# RAM_GPIO.net
KiCad netlist of a schematic drawn in Altium Designer
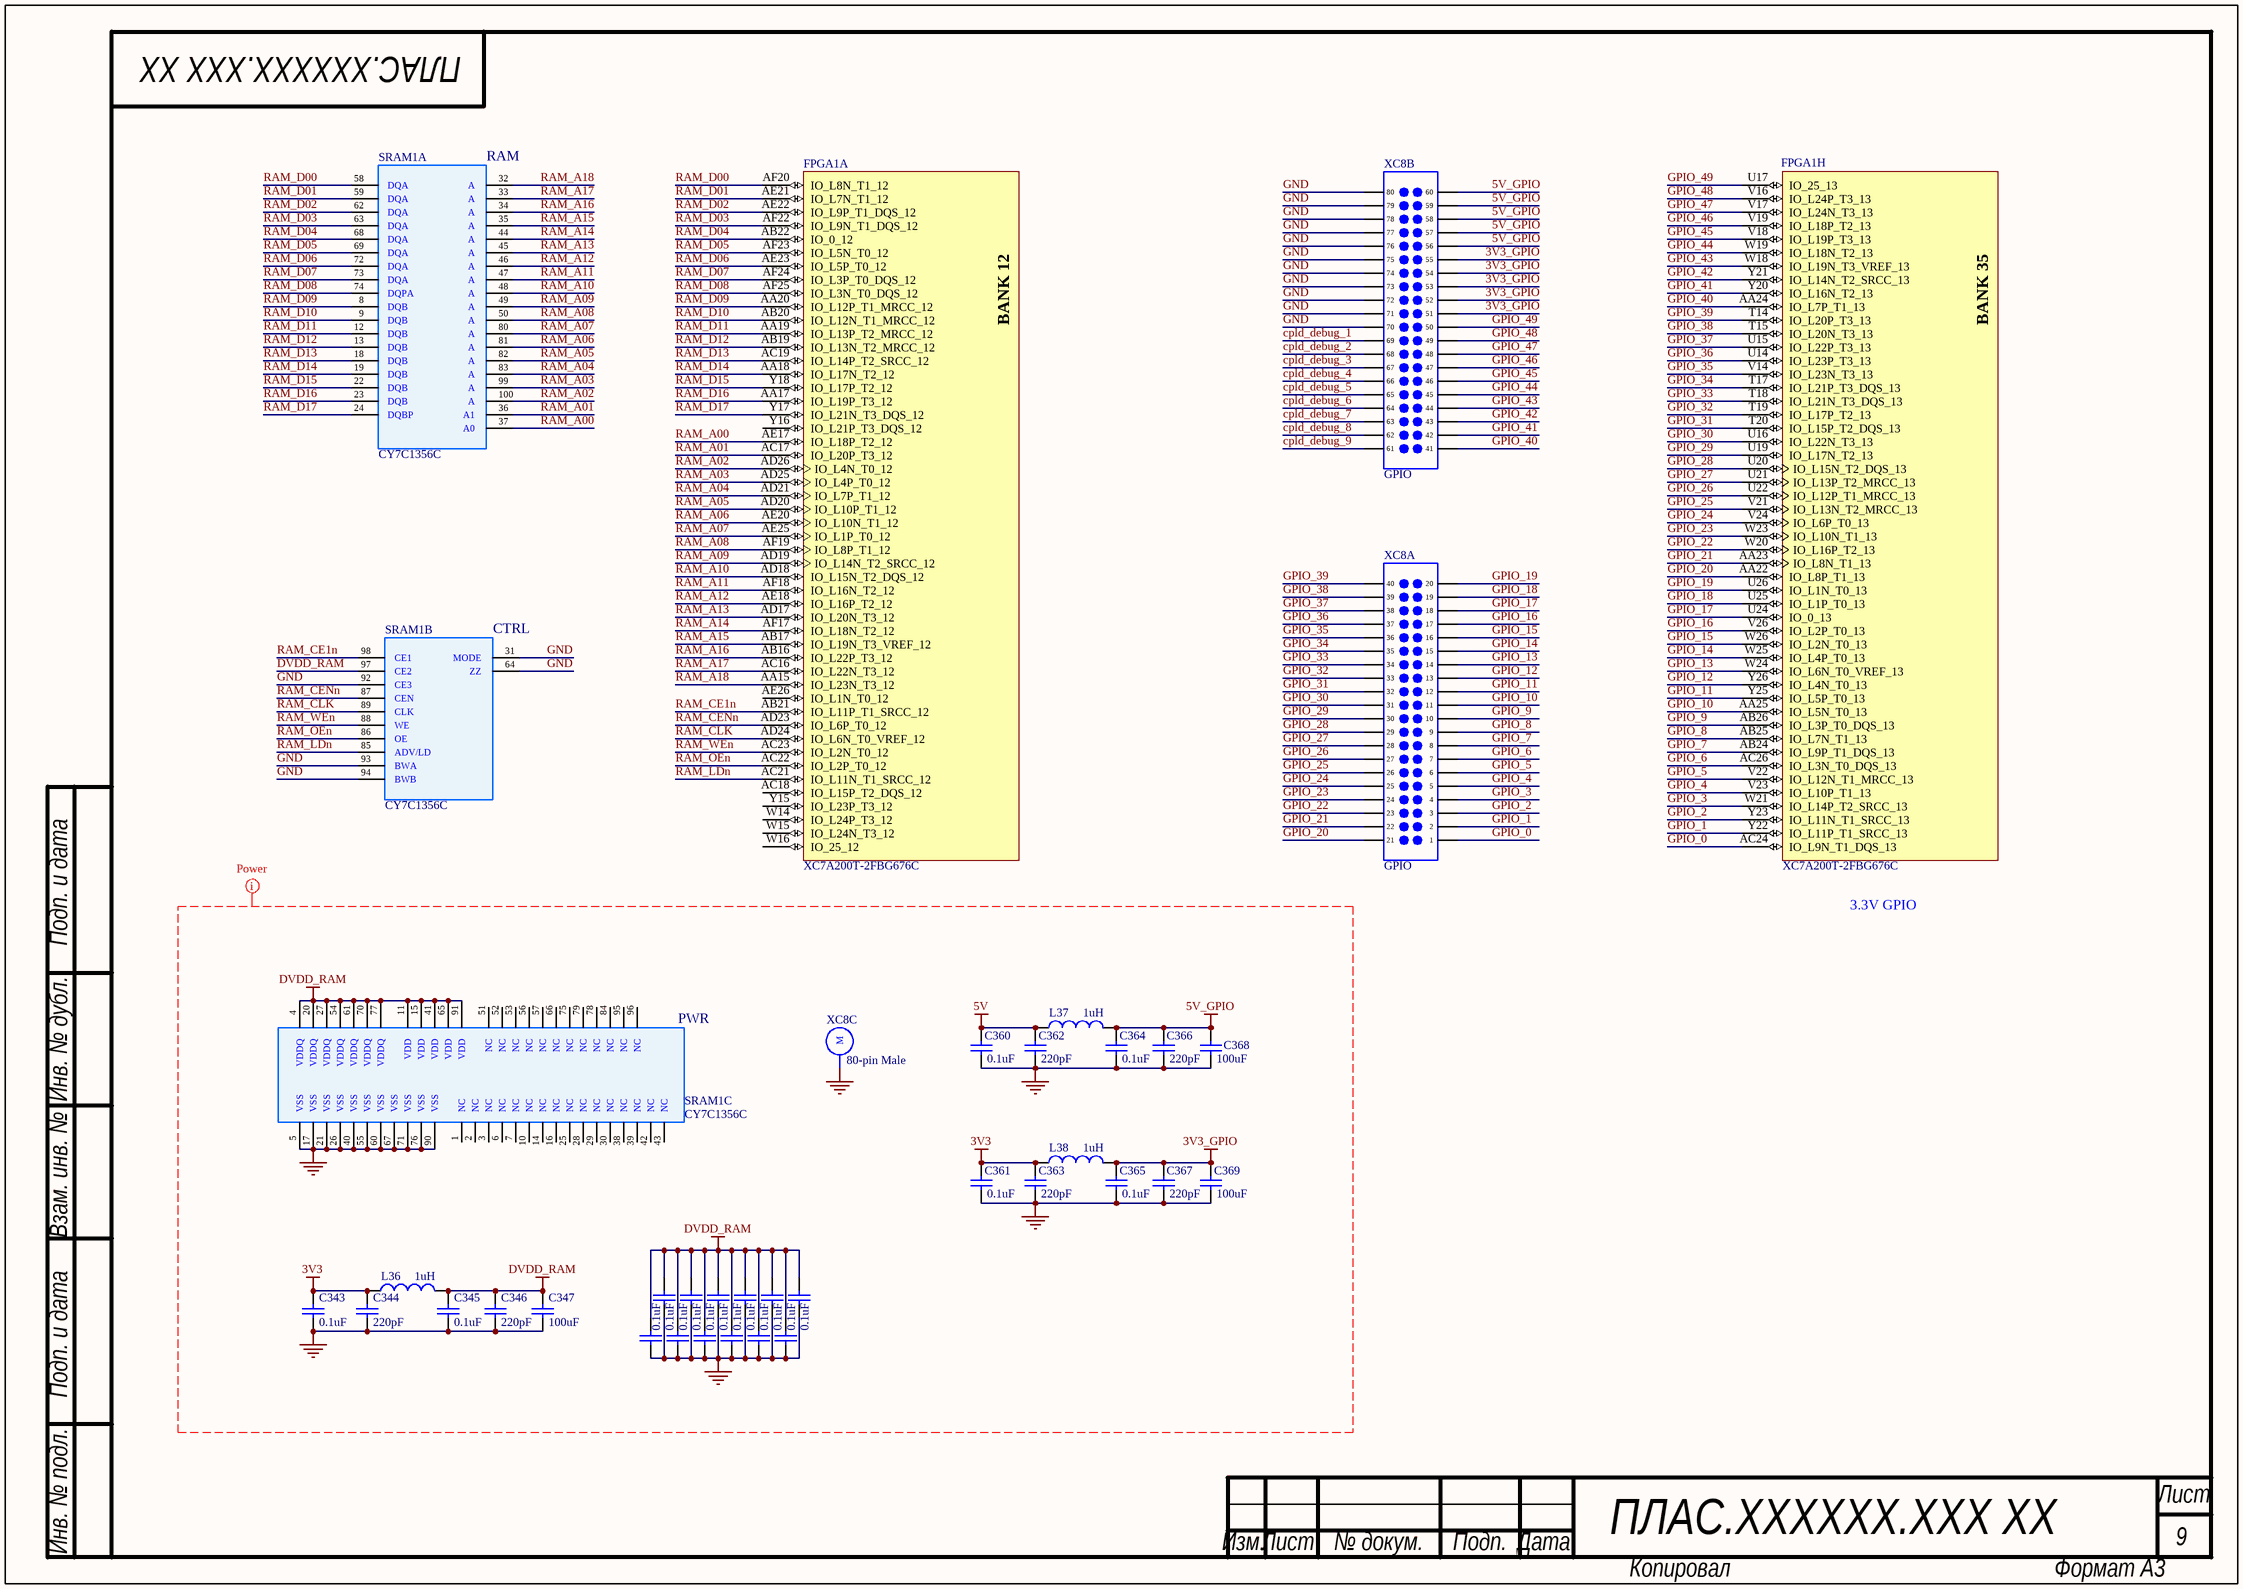
[diagram p0: RAM&GPIO.SchDoc]

(export (version "E")
  (design (tool "Eeschema 10.0.6"))
  (components
    (comp (ref "C343")
      (value "0.1uF")
      (footprint "C0603")
      (description "Cer Cap Small")
      (fields (field (name "MANUFACTURER") "Murata") (field (name "VOLTAGE") "16V"))
      (libsource (lib "USRP2_Clone") (part "Cer Cap"))
    )
    (comp (ref "C344")
      (value "220pF")
      (footprint "C0603")
      (description "Cer Cap Small")
      (fields (field (name "MANUFACTURER") "Murata") (field (name "VOLTAGE") "16V"))
      (libsource (lib "USRP2_Clone") (part "Cer Cap"))
    )
    (comp (ref "C345")
      (value "0.1uF")
      (footprint "C0603")
      (description "Cer Cap Small")
      (fields (field (name "MANUFACTURER") "Murata") (field (name "VOLTAGE") "16V"))
      (libsource (lib "USRP2_Clone") (part "Cer Cap"))
    )
    (comp (ref "C346")
      (value "220pF")
      (footprint "C0603")
      (description "Cer Cap Small")
      (fields (field (name "MANUFACTURER") "Murata") (field (name "VOLTAGE") "16V"))
      (libsource (lib "USRP2_Clone") (part "Cer Cap"))
    )
    (comp (ref "C347")
      (value "100uF")
      (footprint "C1210")
      (description "Cer Cap Large")
      (fields (field (name "MANUFACTURER") "Murata") (field (name "TOLERANCE") "20%"))
      (libsource (lib "USRP2_Clone") (part "Cap uF"))
    )
    (comp (ref "C348")
      (value "0.1uF")
      (footprint "С0402")
      (description "Cer Cap Small")
      (fields (field (name "MANUFACTURER") "Murata") (field (name "VOLTAGE") "50V"))
      (libsource (lib "USRP2_Clone") (part "Cer Cap"))
    )
    (comp (ref "C349")
      (value "0.1uF")
      (footprint "С0402")
      (description "Cer Cap Small")
      (fields (field (name "MANUFACTURER") "Murata") (field (name "VOLTAGE") "50V"))
      (libsource (lib "USRP2_Clone") (part "Cer Cap"))
    )
    (comp (ref "C350")
      (value "0.1uF")
      (footprint "С0402")
      (description "Cer Cap Small")
      (fields (field (name "MANUFACTURER") "Murata") (field (name "VOLTAGE") "50V"))
      (libsource (lib "USRP2_Clone") (part "Cer Cap"))
    )
    (comp (ref "C351")
      (value "0.1uF")
      (footprint "С0402")
      (description "Cer Cap Small")
      (fields (field (name "MANUFACTURER") "Murata") (field (name "VOLTAGE") "50V"))
      (libsource (lib "USRP2_Clone") (part "Cer Cap"))
    )
    (comp (ref "C352")
      (value "0.1uF")
      (footprint "С0402")
      (description "Cer Cap Small")
      (fields (field (name "MANUFACTURER") "Murata") (field (name "VOLTAGE") "50V"))
      (libsource (lib "USRP2_Clone") (part "Cer Cap"))
    )
    (comp (ref "C353")
      (value "0.1uF")
      (footprint "С0402")
      (description "Cer Cap Small")
      (fields (field (name "MANUFACTURER") "Murata") (field (name "VOLTAGE") "50V"))
      (libsource (lib "USRP2_Clone") (part "Cer Cap"))
    )
    (comp (ref "C354")
      (value "0.1uF")
      (footprint "С0402")
      (description "Cer Cap Small")
      (fields (field (name "MANUFACTURER") "Murata") (field (name "VOLTAGE") "50V"))
      (libsource (lib "USRP2_Clone") (part "Cer Cap"))
    )
    (comp (ref "C355")
      (value "0.1uF")
      (footprint "С0402")
      (description "Cer Cap Small")
      (fields (field (name "MANUFACTURER") "Murata") (field (name "VOLTAGE") "50V"))
      (libsource (lib "USRP2_Clone") (part "Cer Cap"))
    )
    (comp (ref "C356")
      (value "0.1uF")
      (footprint "С0402")
      (description "Cer Cap Small")
      (fields (field (name "MANUFACTURER") "Murata") (field (name "VOLTAGE") "50V"))
      (libsource (lib "USRP2_Clone") (part "Cer Cap"))
    )
    (comp (ref "C357")
      (value "0.1uF")
      (footprint "С0402")
      (description "Cer Cap Small")
      (fields (field (name "MANUFACTURER") "Murata") (field (name "VOLTAGE") "50V"))
      (libsource (lib "USRP2_Clone") (part "Cer Cap"))
    )
    (comp (ref "C358")
      (value "0.1uF")
      (footprint "С0402")
      (description "Cer Cap Small")
      (fields (field (name "MANUFACTURER") "Murata") (field (name "VOLTAGE") "50V"))
      (libsource (lib "USRP2_Clone") (part "Cer Cap"))
    )
    (comp (ref "C359")
      (value "0.1uF")
      (footprint "С0402")
      (description "Cer Cap Small")
      (fields (field (name "MANUFACTURER") "Murata") (field (name "VOLTAGE") "50V"))
      (libsource (lib "USRP2_Clone") (part "Cer Cap"))
    )
    (comp (ref "C360")
      (value "0.1uF")
      (footprint "C0603")
      (description "Cer Cap Small")
      (fields (field (name "MANUFACTURER") "Murata") (field (name "VOLTAGE") "16V"))
      (libsource (lib "USRP2_Clone") (part "Cer Cap"))
    )
    (comp (ref "C361")
      (value "0.1uF")
      (footprint "C0603")
      (description "Cer Cap Small")
      (fields (field (name "MANUFACTURER") "Murata") (field (name "VOLTAGE") "16V"))
      (libsource (lib "USRP2_Clone") (part "Cer Cap"))
    )
    (comp (ref "C362")
      (value "220pF")
      (footprint "C0603")
      (description "Cer Cap Small")
      (fields (field (name "MANUFACTURER") "Murata") (field (name "VOLTAGE") "16V"))
      (libsource (lib "USRP2_Clone") (part "Cer Cap"))
    )
    (comp (ref "C363")
      (value "220pF")
      (footprint "C0603")
      (description "Cer Cap Small")
      (fields (field (name "MANUFACTURER") "Murata") (field (name "VOLTAGE") "16V"))
      (libsource (lib "USRP2_Clone") (part "Cer Cap"))
    )
    (comp (ref "C364")
      (value "0.1uF")
      (footprint "C0603")
      (description "Cer Cap Small")
      (fields (field (name "MANUFACTURER") "Murata") (field (name "VOLTAGE") "16V"))
      (libsource (lib "USRP2_Clone") (part "Cer Cap"))
    )
    (comp (ref "C365")
      (value "0.1uF")
      (footprint "C0603")
      (description "Cer Cap Small")
      (fields (field (name "MANUFACTURER") "Murata") (field (name "VOLTAGE") "16V"))
      (libsource (lib "USRP2_Clone") (part "Cer Cap"))
    )
    (comp (ref "C366")
      (value "220pF")
      (footprint "C0603")
      (description "Cer Cap Small")
      (fields (field (name "MANUFACTURER") "Murata") (field (name "VOLTAGE") "16V"))
      (libsource (lib "USRP2_Clone") (part "Cer Cap"))
    )
    (comp (ref "C367")
      (value "220pF")
      (footprint "C0603")
      (description "Cer Cap Small")
      (fields (field (name "MANUFACTURER") "Murata") (field (name "VOLTAGE") "16V"))
      (libsource (lib "USRP2_Clone") (part "Cer Cap"))
    )
    (comp (ref "C368")
      (value "100uF")
      (footprint "C1210")
      (description "Cer Cap Large")
      (fields (field (name "MANUFACTURER") "Murata") (field (name "TOLERANCE") "20%"))
      (libsource (lib "") (part "Cap uF_1"))
    )
    (comp (ref "C369")
      (value "100uF")
      (footprint "C1210")
      (description "Cer Cap Large")
      (fields (field (name "MANUFACTURER") "Murata") (field (name "TOLERANCE") "20%"))
      (libsource (lib "USRP2_Clone") (part "Cap uF"))
    )
    (comp (ref "FPGA1")
      (value "XC7A200T-2FBG676C")
      (footprint "FGG676")
      (description "Artix-7 FPGA, 400 User I/Os, 8 GTP, 676-Ball BGA, Speed Grade 2, Commercial Grade, Pb-Free")
      (fields (field (name "GENERIC PART NUMBER") "XC7A200T") (field (name "MANUFACTURER") "Xilinx"))
      (libsource (lib "") (part "XC7A200T-2FBG676C_1"))
    )
    (comp (ref "L36")
      (value "1uH")
      (footprint "L1210_Murata")
      (description "Inductor_Power_Lines")
      (fields (field (name "TOLERANCE") "5%") (field (name "MANUFACTURER") "Murata"))
      (libsource (lib "USRP2_Clone") (part "Inductor_LF"))
    )
    (comp (ref "L37")
      (value "1uH")
      (footprint "L1210_Murata LQH")
      (description "Inductor_Power_Lines")
      (fields (field (name "TOLERANCE") "5%") (field (name "MANUFACTURER") "Murata"))
      (libsource (lib "USRP2_Clone") (part "Inductor_LF"))
    )
    (comp (ref "L38")
      (value "1uH")
      (footprint "L1210_Murata LQH")
      (description "Inductor_Power_Lines")
      (fields (field (name "TOLERANCE") "5%") (field (name "MANUFACTURER") "Murata"))
      (libsource (lib "USRP2_Clone") (part "Inductor_LF"))
    )
    (comp (ref "SRAM1")
      (value "CY7C1356C")
      (footprint "TQFP-100")
      (description "Pipelined SRAM with NoBL")
      (fields (field (name "VOLTAGE") "3.3 V"))
      (libsource (lib "USRP2_Clone") (part "CY7C1356C"))
    )
    (comp (ref "XC8")
      (value "80-pin Male")
      (footprint "Molex_465572545")
      (description "CONN FML 80POS 4ROWS GOLD SMD")
      (fields (field (name "MANUFACTURER") "Molex"))
      (libsource (lib "USRP2_Clone") (part "Molex_SEARAY™ 46557"))
    )
  )
  (nets
    (net (code "1") (name "/GPIO_0") (class "Default")
      (node (ref "FPGA1") (pin "AC24") (pinfunction "IO_L9N_T1_DQS_13_AC24") (pintype "bidirectional"))
      (node (ref "XC8") (pin "1") (pinfunction "1_1") (pintype "passive"))
    )
    (net (code "2") (name "/GPIO_1") (class "Default")
      (node (ref "FPGA1") (pin "Y22") (pinfunction "IO_L11P_T1_SRCC_13_Y22") (pintype "bidirectional"))
      (node (ref "XC8") (pin "2") (pinfunction "2_2") (pintype "passive"))
    )
    (net (code "3") (name "/GPIO_2") (class "Default")
      (node (ref "FPGA1") (pin "Y23") (pinfunction "IO_L11N_T1_SRCC_13_Y23") (pintype "bidirectional"))
      (node (ref "XC8") (pin "3") (pinfunction "3_3") (pintype "passive"))
    )
    (net (code "4") (name "/GPIO_3") (class "Default")
      (node (ref "FPGA1") (pin "W21") (pinfunction "IO_L14P_T2_SRCC_13_W21") (pintype "bidirectional"))
      (node (ref "XC8") (pin "4") (pinfunction "4_4") (pintype "passive"))
    )
    (net (code "5") (name "/GPIO_4") (class "Default")
      (node (ref "FPGA1") (pin "V23") (pinfunction "IO_L10P_T1_13_V23") (pintype "bidirectional"))
      (node (ref "XC8") (pin "5") (pinfunction "5_5") (pintype "passive"))
    )
    (net (code "6") (name "/GPIO_5") (class "Default")
      (node (ref "FPGA1") (pin "V22") (pinfunction "IO_L12N_T1_MRCC_13_V22") (pintype "bidirectional"))
      (node (ref "XC8") (pin "6") (pinfunction "6_6") (pintype "passive"))
    )
    (net (code "7") (name "/GPIO_6") (class "Default")
      (node (ref "FPGA1") (pin "AC26") (pinfunction "IO_L3N_T0_DQS_13_AC26") (pintype "bidirectional"))
      (node (ref "XC8") (pin "7") (pinfunction "7_7") (pintype "passive"))
    )
    (net (code "8") (name "/GPIO_7") (class "Default")
      (node (ref "FPGA1") (pin "AB24") (pinfunction "IO_L9P_T1_DQS_13_AB24") (pintype "bidirectional"))
      (node (ref "XC8") (pin "8") (pinfunction "8_8") (pintype "passive"))
    )
    (net (code "9") (name "/GPIO_8") (class "Default")
      (node (ref "FPGA1") (pin "AB25") (pinfunction "IO_L7N_T1_13_AB25") (pintype "bidirectional"))
      (node (ref "XC8") (pin "9") (pinfunction "9_9") (pintype "passive"))
    )
    (net (code "10") (name "/GPIO_9") (class "Default")
      (node (ref "FPGA1") (pin "AB26") (pinfunction "IO_L3P_T0_DQS_13_AB26") (pintype "bidirectional"))
      (node (ref "XC8") (pin "10") (pinfunction "10_10") (pintype "passive"))
    )
    (net (code "11") (name "/GPIO_10") (class "Default")
      (node (ref "FPGA1") (pin "AA25") (pinfunction "IO_L5N_T0_13_AA25") (pintype "bidirectional"))
      (node (ref "XC8") (pin "11") (pinfunction "11_11") (pintype "passive"))
    )
    (net (code "12") (name "/GPIO_11") (class "Default")
      (node (ref "FPGA1") (pin "Y25") (pinfunction "IO_L5P_T0_13_Y25") (pintype "bidirectional"))
      (node (ref "XC8") (pin "12") (pinfunction "12_12") (pintype "passive"))
    )
    (net (code "13") (name "/GPIO_12") (class "Default")
      (node (ref "FPGA1") (pin "Y26") (pinfunction "IO_L4N_T0_13_Y26") (pintype "bidirectional"))
      (node (ref "XC8") (pin "13") (pinfunction "13_13") (pintype "passive"))
    )
    (net (code "14") (name "/GPIO_13") (class "Default")
      (node (ref "FPGA1") (pin "W24") (pinfunction "IO_L6N_T0_VREF_13_W24") (pintype "bidirectional"))
      (node (ref "XC8") (pin "14") (pinfunction "14_14") (pintype "passive"))
    )
    (net (code "15") (name "/GPIO_14") (class "Default")
      (node (ref "FPGA1") (pin "W25") (pinfunction "IO_L4P_T0_13_W25") (pintype "bidirectional"))
      (node (ref "XC8") (pin "15") (pinfunction "15_15") (pintype "passive"))
    )
    (net (code "16") (name "/GPIO_15") (class "Default")
      (node (ref "FPGA1") (pin "W26") (pinfunction "IO_L2N_T0_13_W26") (pintype "bidirectional"))
      (node (ref "XC8") (pin "16") (pinfunction "16_16") (pintype "passive"))
    )
    (net (code "17") (name "/GPIO_16") (class "Default")
      (node (ref "FPGA1") (pin "V26") (pinfunction "IO_L2P_T0_13_V26") (pintype "bidirectional"))
      (node (ref "XC8") (pin "17") (pinfunction "17_17") (pintype "passive"))
    )
    (net (code "18") (name "/GPIO_17") (class "Default")
      (node (ref "FPGA1") (pin "U24") (pinfunction "IO_0_13_U24") (pintype "bidirectional"))
      (node (ref "XC8") (pin "18") (pinfunction "18_18") (pintype "passive"))
    )
    (net (code "19") (name "/GPIO_18") (class "Default")
      (node (ref "FPGA1") (pin "U25") (pinfunction "IO_L1P_T0_13_U25") (pintype "bidirectional"))
      (node (ref "XC8") (pin "19") (pinfunction "19_19") (pintype "passive"))
    )
    (net (code "20") (name "/GPIO_19") (class "Default")
      (node (ref "FPGA1") (pin "U26") (pinfunction "IO_L1N_T0_13_U26") (pintype "bidirectional"))
      (node (ref "XC8") (pin "20") (pinfunction "20_20") (pintype "passive"))
    )
    (net (code "21") (name "/GPIO_20") (class "Default")
      (node (ref "FPGA1") (pin "AA22") (pinfunction "IO_L8P_T1_13_AA22") (pintype "bidirectional"))
      (node (ref "XC8") (pin "21") (pinfunction "21_21") (pintype "passive"))
    )
    (net (code "22") (name "/GPIO_21") (class "Default")
      (node (ref "FPGA1") (pin "AA23") (pinfunction "IO_L8N_T1_13_AA23") (pintype "bidirectional"))
      (node (ref "XC8") (pin "22") (pinfunction "22_22") (pintype "passive"))
    )
    (net (code "23") (name "/GPIO_22") (class "Default")
      (node (ref "FPGA1") (pin "W20") (pinfunction "IO_L16P_T2_13_W20") (pintype "bidirectional"))
      (node (ref "XC8") (pin "23") (pinfunction "23_23") (pintype "passive"))
    )
    (net (code "24") (name "/GPIO_23") (class "Default")
      (node (ref "FPGA1") (pin "W23") (pinfunction "IO_L10N_T1_13_W23") (pintype "bidirectional"))
      (node (ref "XC8") (pin "24") (pinfunction "24_24") (pintype "passive"))
    )
    (net (code "25") (name "/GPIO_24") (class "Default")
      (node (ref "FPGA1") (pin "V24") (pinfunction "IO_L6P_T0_13_V24") (pintype "bidirectional"))
      (node (ref "XC8") (pin "25") (pinfunction "25_25") (pintype "passive"))
    )
    (net (code "26") (name "/GPIO_25") (class "Default")
      (node (ref "FPGA1") (pin "V21") (pinfunction "IO_L13N_T2_MRCC_13_V21") (pintype "bidirectional"))
      (node (ref "XC8") (pin "26") (pinfunction "26_26") (pintype "passive"))
    )
    (net (code "27") (name "/GPIO_26") (class "Default")
      (node (ref "FPGA1") (pin "U22") (pinfunction "IO_L12P_T1_MRCC_13_U22") (pintype "bidirectional"))
      (node (ref "XC8") (pin "27") (pinfunction "27_27") (pintype "passive"))
    )
    (net (code "28") (name "/GPIO_27") (class "Default")
      (node (ref "FPGA1") (pin "U21") (pinfunction "IO_L13P_T2_MRCC_13_U21") (pintype "bidirectional"))
      (node (ref "XC8") (pin "28") (pinfunction "28_28") (pintype "passive"))
    )
    (net (code "29") (name "/GPIO_28") (class "Default")
      (node (ref "FPGA1") (pin "U20") (pinfunction "IO_L15N_T2_DQS_13_U20") (pintype "bidirectional"))
      (node (ref "XC8") (pin "29") (pinfunction "29_29") (pintype "passive"))
    )
    (net (code "30") (name "/GPIO_29") (class "Default")
      (node (ref "FPGA1") (pin "U19") (pinfunction "IO_L17N_T2_13_U19") (pintype "bidirectional"))
      (node (ref "XC8") (pin "30") (pinfunction "30_30") (pintype "passive"))
    )
    (net (code "31") (name "/GPIO_30") (class "Default")
      (node (ref "FPGA1") (pin "U16") (pinfunction "IO_L22N_T3_13_U16") (pintype "bidirectional"))
      (node (ref "XC8") (pin "31") (pinfunction "31_31") (pintype "passive"))
    )
    (net (code "32") (name "/GPIO_31") (class "Default")
      (node (ref "FPGA1") (pin "T20") (pinfunction "IO_L15P_T2_DQS_13_T20") (pintype "bidirectional"))
      (node (ref "XC8") (pin "32") (pinfunction "32_32") (pintype "passive"))
    )
    (net (code "33") (name "/GPIO_32") (class "Default")
      (node (ref "FPGA1") (pin "T19") (pinfunction "IO_L17P_T2_13_T19") (pintype "bidirectional"))
      (node (ref "XC8") (pin "33") (pinfunction "33_33") (pintype "passive"))
    )
    (net (code "34") (name "/GPIO_33") (class "Default")
      (node (ref "FPGA1") (pin "T18") (pinfunction "IO_L21N_T3_DQS_13_T18") (pintype "bidirectional"))
      (node (ref "XC8") (pin "34") (pinfunction "34_34") (pintype "passive"))
    )
    (net (code "35") (name "/GPIO_34") (class "Default")
      (node (ref "FPGA1") (pin "T17") (pinfunction "IO_L21P_T3_DQS_13_T17") (pintype "bidirectional"))
      (node (ref "XC8") (pin "35") (pinfunction "35_35") (pintype "passive"))
    )
    (net (code "36") (name "/GPIO_35") (class "Default")
      (node (ref "FPGA1") (pin "V14") (pinfunction "IO_L23N_T3_13_V14") (pintype "bidirectional"))
      (node (ref "XC8") (pin "36") (pinfunction "36_36") (pintype "passive"))
    )
    (net (code "37") (name "/GPIO_36") (class "Default")
      (node (ref "FPGA1") (pin "U14") (pinfunction "IO_L23P_T3_13_U14") (pintype "bidirectional"))
      (node (ref "XC8") (pin "37") (pinfunction "37_37") (pintype "passive"))
    )
    (net (code "38") (name "/GPIO_37") (class "Default")
      (node (ref "FPGA1") (pin "U15") (pinfunction "IO_L22P_T3_13_U15") (pintype "bidirectional"))
      (node (ref "XC8") (pin "38") (pinfunction "38_38") (pintype "passive"))
    )
    (net (code "39") (name "/GPIO_38") (class "Default")
      (node (ref "FPGA1") (pin "T15") (pinfunction "IO_L20N_T3_13_T15") (pintype "bidirectional"))
      (node (ref "XC8") (pin "39") (pinfunction "39_39") (pintype "passive"))
    )
    (net (code "40") (name "/GPIO_39") (class "Default")
      (node (ref "FPGA1") (pin "T14") (pinfunction "IO_L20P_T3_13_T14") (pintype "bidirectional"))
      (node (ref "XC8") (pin "40") (pinfunction "40_40") (pintype "passive"))
    )
    (net (code "41") (name "/GPIO_40") (class "Default")
      (node (ref "FPGA1") (pin "AA24") (pinfunction "IO_L7P_T1_13_AA24") (pintype "bidirectional"))
      (node (ref "XC8") (pin "41") (pinfunction "41_41") (pintype "passive"))
    )
    (net (code "42") (name "/GPIO_41") (class "Default")
      (node (ref "FPGA1") (pin "Y20") (pinfunction "IO_L16N_T2_13_Y20") (pintype "bidirectional"))
      (node (ref "XC8") (pin "42") (pinfunction "42_42") (pintype "passive"))
    )
    (net (code "43") (name "/GPIO_42") (class "Default")
      (node (ref "FPGA1") (pin "Y21") (pinfunction "IO_L14N_T2_SRCC_13_Y21") (pintype "bidirectional"))
      (node (ref "XC8") (pin "43") (pinfunction "43_43") (pintype "passive"))
    )
    (net (code "44") (name "/GPIO_43") (class "Default")
      (node (ref "FPGA1") (pin "W18") (pinfunction "IO_L19N_T3_VREF_13_W18") (pintype "bidirectional"))
      (node (ref "XC8") (pin "44") (pinfunction "44_44") (pintype "passive"))
    )
    (net (code "45") (name "/GPIO_44") (class "Default")
      (node (ref "FPGA1") (pin "W19") (pinfunction "IO_L18N_T2_13_W19") (pintype "bidirectional"))
      (node (ref "XC8") (pin "45") (pinfunction "45_45") (pintype "passive"))
    )
    (net (code "46") (name "/GPIO_45") (class "Default")
      (node (ref "FPGA1") (pin "V18") (pinfunction "IO_L19P_T3_13_V18") (pintype "bidirectional"))
      (node (ref "XC8") (pin "46") (pinfunction "46_46") (pintype "passive"))
    )
    (net (code "47") (name "/GPIO_46") (class "Default")
      (node (ref "FPGA1") (pin "V19") (pinfunction "IO_L18P_T2_13_V19") (pintype "bidirectional"))
      (node (ref "XC8") (pin "47") (pinfunction "47_47") (pintype "passive"))
    )
    (net (code "48") (name "/GPIO_47") (class "Default")
      (node (ref "FPGA1") (pin "V17") (pinfunction "IO_L24N_T3_13_V17") (pintype "bidirectional"))
      (node (ref "XC8") (pin "48") (pinfunction "48_48") (pintype "passive"))
    )
    (net (code "49") (name "/GPIO_48") (class "Default")
      (node (ref "FPGA1") (pin "V16") (pinfunction "IO_L24P_T3_13_V16") (pintype "bidirectional"))
      (node (ref "XC8") (pin "49") (pinfunction "49_49") (pintype "passive"))
    )
    (net (code "50") (name "/GPIO_49") (class "Default")
      (node (ref "FPGA1") (pin "U17") (pinfunction "IO_25_13_U17") (pintype "bidirectional"))
      (node (ref "XC8") (pin "50") (pinfunction "50_50") (pintype "passive"))
    )
    (net (code "51") (name "/RAM_A00") (class "Default")
      (node (ref "FPGA1") (pin "AE17") (pinfunction "IO_L18P_T2_12_AE17") (pintype "bidirectional"))
      (node (ref "SRAM1") (pin "37") (pinfunction "A0_37") (pintype "passive"))
    )
    (net (code "52") (name "/RAM_A01") (class "Default")
      (node (ref "FPGA1") (pin "AC17") (pinfunction "IO_L20P_T3_12_AC17") (pintype "bidirectional"))
      (node (ref "SRAM1") (pin "36") (pinfunction "A1_36") (pintype "passive"))
    )
    (net (code "53") (name "/RAM_A02") (class "Default")
      (node (ref "FPGA1") (pin "AD26") (pinfunction "IO_L4N_T0_12_AD26") (pintype "bidirectional"))
      (node (ref "SRAM1") (pin "100") (pinfunction "A_100") (pintype "passive"))
    )
    (net (code "54") (name "/RAM_A03") (class "Default")
      (node (ref "FPGA1") (pin "AD25") (pinfunction "IO_L4P_T0_12_AD25") (pintype "bidirectional"))
      (node (ref "SRAM1") (pin "99") (pinfunction "A_99") (pintype "passive"))
    )
    (net (code "55") (name "/RAM_A04") (class "Default")
      (node (ref "FPGA1") (pin "AD21") (pinfunction "IO_L7P_T1_12_AD21") (pintype "bidirectional"))
      (node (ref "SRAM1") (pin "83") (pinfunction "A_83") (pintype "passive"))
    )
    (net (code "56") (name "/RAM_A05") (class "Default")
      (node (ref "FPGA1") (pin "AD20") (pinfunction "IO_L10P_T1_12_AD20") (pintype "bidirectional"))
      (node (ref "SRAM1") (pin "82") (pinfunction "A_82") (pintype "passive"))
    )
    (net (code "57") (name "/RAM_A06") (class "Default")
      (node (ref "FPGA1") (pin "AE20") (pinfunction "IO_L10N_T1_12_AE20") (pintype "bidirectional"))
      (node (ref "SRAM1") (pin "81") (pinfunction "A_81") (pintype "passive"))
    )
    (net (code "58") (name "/RAM_A07") (class "Default")
      (node (ref "FPGA1") (pin "AE25") (pinfunction "IO_L1P_T0_12_AE25") (pintype "bidirectional"))
      (node (ref "SRAM1") (pin "80") (pinfunction "A_80") (pintype "passive"))
    )
    (net (code "59") (name "/RAM_A08") (class "Default")
      (node (ref "FPGA1") (pin "AF19") (pinfunction "IO_L8P_T1_12_AF19") (pintype "bidirectional"))
      (node (ref "SRAM1") (pin "50") (pinfunction "A_50") (pintype "passive"))
    )
    (net (code "60") (name "/RAM_A09") (class "Default")
      (node (ref "FPGA1") (pin "AD19") (pinfunction "IO_L14N_T2_SRCC_12_AD19") (pintype "bidirectional"))
      (node (ref "SRAM1") (pin "49") (pinfunction "A_49") (pintype "passive"))
    )
    (net (code "61") (name "/RAM_A10") (class "Default")
      (node (ref "FPGA1") (pin "AD18") (pinfunction "IO_L15N_T2_DQS_12_AD18") (pintype "bidirectional"))
      (node (ref "SRAM1") (pin "48") (pinfunction "A_48") (pintype "passive"))
    )
    (net (code "62") (name "/RAM_A11") (class "Default")
      (node (ref "FPGA1") (pin "AF18") (pinfunction "IO_L16N_T2_12_AF18") (pintype "bidirectional"))
      (node (ref "SRAM1") (pin "47") (pinfunction "A_47") (pintype "passive"))
    )
    (net (code "63") (name "/RAM_A12") (class "Default")
      (node (ref "FPGA1") (pin "AE18") (pinfunction "IO_L16P_T2_12_AE18") (pintype "bidirectional"))
      (node (ref "SRAM1") (pin "46") (pinfunction "A_46") (pintype "passive"))
    )
    (net (code "64") (name "/RAM_A13") (class "Default")
      (node (ref "FPGA1") (pin "AD17") (pinfunction "IO_L20N_T3_12_AD17") (pintype "bidirectional"))
      (node (ref "SRAM1") (pin "45") (pinfunction "A_45") (pintype "passive"))
    )
    (net (code "65") (name "/RAM_A14") (class "Default")
      (node (ref "FPGA1") (pin "AF17") (pinfunction "IO_L18N_T2_12_AF17") (pintype "bidirectional"))
      (node (ref "SRAM1") (pin "44") (pinfunction "A_44") (pintype "passive"))
    )
    (net (code "66") (name "/RAM_A15") (class "Default")
      (node (ref "FPGA1") (pin "AB17") (pinfunction "IO_L19N_T3_VREF_12_AB17") (pintype "bidirectional"))
      (node (ref "SRAM1") (pin "35") (pinfunction "A_35") (pintype "passive"))
    )
    (net (code "67") (name "/RAM_A16") (class "Default")
      (node (ref "FPGA1") (pin "AB16") (pinfunction "IO_L22P_T3_12_AB16") (pintype "bidirectional"))
      (node (ref "SRAM1") (pin "34") (pinfunction "A_34") (pintype "passive"))
    )
    (net (code "68") (name "/RAM_A17") (class "Default")
      (node (ref "FPGA1") (pin "AC16") (pinfunction "IO_L22N_T3_12_AC16") (pintype "bidirectional"))
      (node (ref "SRAM1") (pin "33") (pinfunction "A_33") (pintype "passive"))
    )
    (net (code "69") (name "/RAM_A18") (class "Default")
      (node (ref "FPGA1") (pin "AA15") (pinfunction "IO_L23N_T3_12_AA15") (pintype "bidirectional"))
      (node (ref "SRAM1") (pin "32") (pinfunction "A_32") (pintype "passive"))
    )
    (net (code "70") (name "/RAM_CE1n") (class "Default")
      (node (ref "FPGA1") (pin "AB21") (pinfunction "IO_L11P_T1_SRCC_12_AB21") (pintype "bidirectional"))
      (node (ref "SRAM1") (pin "98") (pinfunction "CE1_98") (pintype "passive"))
    )
    (net (code "71") (name "/RAM_CENn") (class "Default")
      (node (ref "FPGA1") (pin "AD23") (pinfunction "IO_L6P_T0_12_AD23") (pintype "bidirectional"))
      (node (ref "SRAM1") (pin "87") (pinfunction "CEN_87") (pintype "passive"))
    )
    (net (code "72") (name "/RAM_CLK") (class "Default")
      (node (ref "FPGA1") (pin "AD24") (pinfunction "IO_L6N_T0_VREF_12_AD24") (pintype "bidirectional"))
      (node (ref "SRAM1") (pin "89") (pinfunction "CLK_89") (pintype "passive"))
    )
    (net (code "73") (name "/RAM_D00") (class "Default")
      (node (ref "FPGA1") (pin "AF20") (pinfunction "IO_L8N_T1_12_AF20") (pintype "bidirectional"))
      (node (ref "SRAM1") (pin "58") (pinfunction "DQA_58") (pintype "passive"))
    )
    (net (code "74") (name "/RAM_D01") (class "Default")
      (node (ref "FPGA1") (pin "AE21") (pinfunction "IO_L7N_T1_12_AE21") (pintype "bidirectional"))
      (node (ref "SRAM1") (pin "59") (pinfunction "DQA_59") (pintype "passive"))
    )
    (net (code "75") (name "/RAM_D02") (class "Default")
      (node (ref "FPGA1") (pin "AE22") (pinfunction "IO_L9P_T1_DQS_12_AE22") (pintype "bidirectional"))
      (node (ref "SRAM1") (pin "62") (pinfunction "DQA_62") (pintype "passive"))
    )
    (net (code "76") (name "/RAM_D03") (class "Default")
      (node (ref "FPGA1") (pin "AF22") (pinfunction "IO_L9N_T1_DQS_12_AF22") (pintype "bidirectional"))
      (node (ref "SRAM1") (pin "63") (pinfunction "DQA_63") (pintype "passive"))
    )
    (net (code "77") (name "/RAM_D04") (class "Default")
      (node (ref "FPGA1") (pin "AB22") (pinfunction "IO_0_12_AB22") (pintype "bidirectional"))
      (node (ref "SRAM1") (pin "68") (pinfunction "DQA_68") (pintype "passive"))
    )
    (net (code "78") (name "/RAM_D05") (class "Default")
      (node (ref "FPGA1") (pin "AF23") (pinfunction "IO_L5N_T0_12_AF23") (pintype "bidirectional"))
      (node (ref "SRAM1") (pin "69") (pinfunction "DQA_69") (pintype "passive"))
    )
    (net (code "79") (name "/RAM_D06") (class "Default")
      (node (ref "FPGA1") (pin "AE23") (pinfunction "IO_L5P_T0_12_AE23") (pintype "bidirectional"))
      (node (ref "SRAM1") (pin "72") (pinfunction "DQA_72") (pintype "passive"))
    )
    (net (code "80") (name "/RAM_D07") (class "Default")
      (node (ref "FPGA1") (pin "AF24") (pinfunction "IO_L3P_T0_DQS_12_AF24") (pintype "bidirectional"))
      (node (ref "SRAM1") (pin "73") (pinfunction "DQA_73") (pintype "passive"))
    )
    (net (code "81") (name "/RAM_D08") (class "Default")
      (node (ref "FPGA1") (pin "AF25") (pinfunction "IO_L3N_T0_DQS_12_AF25") (pintype "bidirectional"))
      (node (ref "SRAM1") (pin "74") (pinfunction "DQPA_74") (pintype "passive"))
    )
    (net (code "82") (name "/RAM_D09") (class "Default")
      (node (ref "FPGA1") (pin "AA20") (pinfunction "IO_L12P_T1_MRCC_12_AA20") (pintype "bidirectional"))
      (node (ref "SRAM1") (pin "8") (pinfunction "DQB_8") (pintype "passive"))
    )
    (net (code "83") (name "/RAM_D10") (class "Default")
      (node (ref "FPGA1") (pin "AB20") (pinfunction "IO_L12N_T1_MRCC_12_AB20") (pintype "bidirectional"))
      (node (ref "SRAM1") (pin "9") (pinfunction "DQB_9") (pintype "passive"))
    )
    (net (code "84") (name "/RAM_D11") (class "Default")
      (node (ref "FPGA1") (pin "AA19") (pinfunction "IO_L13P_T2_MRCC_12_AA19") (pintype "bidirectional"))
      (node (ref "SRAM1") (pin "12") (pinfunction "DQB_12") (pintype "passive"))
    )
    (net (code "85") (name "/RAM_D12") (class "Default")
      (node (ref "FPGA1") (pin "AB19") (pinfunction "IO_L13N_T2_MRCC_12_AB19") (pintype "bidirectional"))
      (node (ref "SRAM1") (pin "13") (pinfunction "DQB_13") (pintype "passive"))
    )
    (net (code "86") (name "/RAM_D13") (class "Default")
      (node (ref "FPGA1") (pin "AC19") (pinfunction "IO_L14P_T2_SRCC_12_AC19") (pintype "bidirectional"))
      (node (ref "SRAM1") (pin "18") (pinfunction "DQB_18") (pintype "passive"))
    )
    (net (code "87") (name "/RAM_D14") (class "Default")
      (node (ref "FPGA1") (pin "AA18") (pinfunction "IO_L17N_T2_12_AA18") (pintype "bidirectional"))
      (node (ref "SRAM1") (pin "19") (pinfunction "DQB_19") (pintype "passive"))
    )
    (net (code "88") (name "/RAM_D15") (class "Default")
      (node (ref "FPGA1") (pin "Y18") (pinfunction "IO_L17P_T2_12_Y18") (pintype "bidirectional"))
      (node (ref "SRAM1") (pin "22") (pinfunction "DQB_22") (pintype "passive"))
    )
    (net (code "89") (name "/RAM_D16") (class "Default")
      (node (ref "FPGA1") (pin "AA17") (pinfunction "IO_L19P_T3_12_AA17") (pintype "bidirectional"))
      (node (ref "SRAM1") (pin "23") (pinfunction "DQB_23") (pintype "passive"))
    )
    (net (code "90") (name "/RAM_D17") (class "Default")
      (node (ref "FPGA1") (pin "Y17") (pinfunction "IO_L21N_T3_DQS_12_Y17") (pintype "bidirectional"))
      (node (ref "SRAM1") (pin "24") (pinfunction "DQBP_24") (pintype "passive"))
    )
    (net (code "91") (name "/RAM_LDn") (class "Default")
      (node (ref "FPGA1") (pin "AC21") (pinfunction "IO_L11N_T1_SRCC_12_AC21") (pintype "bidirectional"))
      (node (ref "SRAM1") (pin "85") (pinfunction "ADV/LD_85") (pintype "passive"))
    )
    (net (code "92") (name "/RAM_OEn") (class "Default")
      (node (ref "FPGA1") (pin "AC22") (pinfunction "IO_L2P_T0_12_AC22") (pintype "bidirectional"))
      (node (ref "SRAM1") (pin "86") (pinfunction "OE_86") (pintype "passive"))
    )
    (net (code "93") (name "/RAM_WEn") (class "Default")
      (node (ref "FPGA1") (pin "AC23") (pinfunction "IO_L2N_T0_12_AC23") (pintype "bidirectional"))
      (node (ref "SRAM1") (pin "88") (pinfunction "WE_88") (pintype "passive"))
    )
    (net (code "94") (name "/cpld_debug_1") (class "Default")
      (node (ref "XC8") (pin "69") (pinfunction "69_69") (pintype "passive"))
    )
    (net (code "95") (name "/cpld_debug_2") (class "Default")
      (node (ref "XC8") (pin "68") (pinfunction "68_68") (pintype "passive"))
    )
    (net (code "96") (name "/cpld_debug_3") (class "Default")
      (node (ref "XC8") (pin "67") (pinfunction "67_67") (pintype "passive"))
    )
    (net (code "97") (name "/cpld_debug_4") (class "Default")
      (node (ref "XC8") (pin "66") (pinfunction "66_66") (pintype "passive"))
    )
    (net (code "98") (name "/cpld_debug_5") (class "Default")
      (node (ref "XC8") (pin "65") (pinfunction "65_65") (pintype "passive"))
    )
    (net (code "99") (name "/cpld_debug_6") (class "Default")
      (node (ref "XC8") (pin "64") (pinfunction "64_64") (pintype "passive"))
    )
    (net (code "100") (name "/cpld_debug_7") (class "Default")
      (node (ref "XC8") (pin "63") (pinfunction "63_63") (pintype "passive"))
    )
    (net (code "101") (name "/cpld_debug_8") (class "Default")
      (node (ref "XC8") (pin "62") (pinfunction "62_62") (pintype "passive"))
    )
    (net (code "102") (name "/cpld_debug_9") (class "Default")
      (node (ref "XC8") (pin "61") (pinfunction "61_61") (pintype "passive"))
    )
    (net (code "103") (name "3V3") (class "Default")
      (node (ref "C343") (pin "1") (pinfunction "1_1") (pintype "passive"))
      (node (ref "C344") (pin "1") (pinfunction "1_1") (pintype "passive"))
      (node (ref "C361") (pin "1") (pinfunction "1_1") (pintype "passive"))
      (node (ref "C363") (pin "1") (pinfunction "1_1") (pintype "passive"))
      (node (ref "L36") (pin "2") (pinfunction "2_2") (pintype "passive"))
      (node (ref "L38") (pin "2") (pinfunction "2_2") (pintype "passive"))
    )
    (net (code "104") (name "3V3_GPIO") (class "Default")
      (node (ref "C365") (pin "1") (pinfunction "1_1") (pintype "passive"))
      (node (ref "C367") (pin "1") (pinfunction "1_1") (pintype "passive"))
      (node (ref "C369") (pin "2") (pinfunction "2_2") (pintype "passive"))
      (node (ref "L38") (pin "1") (pinfunction "1_1") (pintype "passive"))
      (node (ref "XC8") (pin "51") (pinfunction "51_51") (pintype "passive"))
      (node (ref "XC8") (pin "52") (pinfunction "52_52") (pintype "passive"))
      (node (ref "XC8") (pin "53") (pinfunction "53_53") (pintype "passive"))
      (node (ref "XC8") (pin "54") (pinfunction "54_54") (pintype "passive"))
      (node (ref "XC8") (pin "55") (pinfunction "55_55") (pintype "passive"))
    )
    (net (code "105") (name "5V") (class "Default")
      (node (ref "C360") (pin "1") (pinfunction "1_1") (pintype "passive"))
      (node (ref "C362") (pin "1") (pinfunction "1_1") (pintype "passive"))
      (node (ref "L37") (pin "2") (pinfunction "2_2") (pintype "passive"))
    )
    (net (code "106") (name "5V_GPIO") (class "Default")
      (node (ref "C364") (pin "1") (pinfunction "1_1") (pintype "passive"))
      (node (ref "C366") (pin "1") (pinfunction "1_1") (pintype "passive"))
      (node (ref "C368") (pin "1") (pinfunction "1_1") (pintype "passive"))
      (node (ref "L37") (pin "1") (pinfunction "1_1") (pintype "passive"))
      (node (ref "XC8") (pin "56") (pinfunction "56_56") (pintype "passive"))
      (node (ref "XC8") (pin "57") (pinfunction "57_57") (pintype "passive"))
      (node (ref "XC8") (pin "58") (pinfunction "58_58") (pintype "passive"))
      (node (ref "XC8") (pin "59") (pinfunction "59_59") (pintype "passive"))
      (node (ref "XC8") (pin "60") (pinfunction "60_60") (pintype "passive"))
    )
    (net (code "107") (name "DVDD_RAM") (class "Default")
      (node (ref "C345") (pin "1") (pinfunction "1_1") (pintype "passive"))
      (node (ref "C346") (pin "1") (pinfunction "1_1") (pintype "passive"))
      (node (ref "C347") (pin "2") (pinfunction "2_2") (pintype "passive"))
      (node (ref "C348") (pin "2") (pinfunction "2_2") (pintype "passive"))
      (node (ref "C349") (pin "2") (pinfunction "2_2") (pintype "passive"))
      (node (ref "C350") (pin "2") (pinfunction "2_2") (pintype "passive"))
      (node (ref "C351") (pin "2") (pinfunction "2_2") (pintype "passive"))
      (node (ref "C352") (pin "2") (pinfunction "2_2") (pintype "passive"))
      (node (ref "C353") (pin "2") (pinfunction "2_2") (pintype "passive"))
      (node (ref "C354") (pin "2") (pinfunction "2_2") (pintype "passive"))
      (node (ref "C355") (pin "2") (pinfunction "2_2") (pintype "passive"))
      (node (ref "C356") (pin "2") (pinfunction "2_2") (pintype "passive"))
      (node (ref "C357") (pin "2") (pinfunction "2_2") (pintype "passive"))
      (node (ref "C358") (pin "2") (pinfunction "2_2") (pintype "passive"))
      (node (ref "C359") (pin "2") (pinfunction "2_2") (pintype "passive"))
      (node (ref "L36") (pin "1") (pinfunction "1_1") (pintype "passive"))
      (node (ref "SRAM1") (pin "11") (pinfunction "VDD_11") (pintype "passive"))
      (node (ref "SRAM1") (pin "15") (pinfunction "VDD_15") (pintype "passive"))
      (node (ref "SRAM1") (pin "20") (pinfunction "VDDQ_20") (pintype "passive"))
      (node (ref "SRAM1") (pin "27") (pinfunction "VDDQ_27") (pintype "passive"))
      (node (ref "SRAM1") (pin "4") (pinfunction "VDDQ_4") (pintype "passive"))
      (node (ref "SRAM1") (pin "41") (pinfunction "VDD_41") (pintype "passive"))
      (node (ref "SRAM1") (pin "54") (pinfunction "VDDQ_54") (pintype "passive"))
      (node (ref "SRAM1") (pin "61") (pinfunction "VDDQ_61") (pintype "passive"))
      (node (ref "SRAM1") (pin "65") (pinfunction "VDD_65") (pintype "passive"))
      (node (ref "SRAM1") (pin "70") (pinfunction "VDDQ_70") (pintype "passive"))
      (node (ref "SRAM1") (pin "77") (pinfunction "VDDQ_77") (pintype "passive"))
      (node (ref "SRAM1") (pin "91") (pinfunction "VDD_91") (pintype "passive"))
      (node (ref "SRAM1") (pin "97") (pinfunction "CE2_97") (pintype "passive"))
    )
    (net (code "108") (name "GND") (class "Default")
      (node (ref "C343") (pin "2") (pinfunction "2_2") (pintype "passive"))
      (node (ref "C344") (pin "2") (pinfunction "2_2") (pintype "passive"))
      (node (ref "C345") (pin "2") (pinfunction "2_2") (pintype "passive"))
      (node (ref "C346") (pin "2") (pinfunction "2_2") (pintype "passive"))
      (node (ref "C347") (pin "1") (pinfunction "1_1") (pintype "passive"))
      (node (ref "C348") (pin "1") (pinfunction "1_1") (pintype "passive"))
      (node (ref "C349") (pin "1") (pinfunction "1_1") (pintype "passive"))
      (node (ref "C350") (pin "1") (pinfunction "1_1") (pintype "passive"))
      (node (ref "C351") (pin "1") (pinfunction "1_1") (pintype "passive"))
      (node (ref "C352") (pin "1") (pinfunction "1_1") (pintype "passive"))
      (node (ref "C353") (pin "1") (pinfunction "1_1") (pintype "passive"))
      (node (ref "C354") (pin "1") (pinfunction "1_1") (pintype "passive"))
      (node (ref "C355") (pin "1") (pinfunction "1_1") (pintype "passive"))
      (node (ref "C356") (pin "1") (pinfunction "1_1") (pintype "passive"))
      (node (ref "C357") (pin "1") (pinfunction "1_1") (pintype "passive"))
      (node (ref "C358") (pin "1") (pinfunction "1_1") (pintype "passive"))
      (node (ref "C359") (pin "1") (pinfunction "1_1") (pintype "passive"))
      (node (ref "C360") (pin "2") (pinfunction "2_2") (pintype "passive"))
      (node (ref "C361") (pin "2") (pinfunction "2_2") (pintype "passive"))
      (node (ref "C362") (pin "2") (pinfunction "2_2") (pintype "passive"))
      (node (ref "C363") (pin "2") (pinfunction "2_2") (pintype "passive"))
      (node (ref "C364") (pin "2") (pinfunction "2_2") (pintype "passive"))
      (node (ref "C365") (pin "2") (pinfunction "2_2") (pintype "passive"))
      (node (ref "C366") (pin "2") (pinfunction "2_2") (pintype "passive"))
      (node (ref "C367") (pin "2") (pinfunction "2_2") (pintype "passive"))
      (node (ref "C368") (pin "2") (pinfunction "2_2") (pintype "passive"))
      (node (ref "C369") (pin "1") (pinfunction "1_1") (pintype "passive"))
      (node (ref "SRAM1") (pin "17") (pinfunction "VSS_17") (pintype "passive"))
      (node (ref "SRAM1") (pin "21") (pinfunction "VSS_21") (pintype "passive"))
      (node (ref "SRAM1") (pin "26") (pinfunction "VSS_26") (pintype "passive"))
      (node (ref "SRAM1") (pin "31") (pinfunction "MODE_31") (pintype "passive"))
      (node (ref "SRAM1") (pin "40") (pinfunction "VSS_40") (pintype "passive"))
      (node (ref "SRAM1") (pin "5") (pinfunction "VSS_5") (pintype "passive"))
      (node (ref "SRAM1") (pin "55") (pinfunction "VSS_55") (pintype "passive"))
      (node (ref "SRAM1") (pin "60") (pinfunction "VSS_60") (pintype "passive"))
      (node (ref "SRAM1") (pin "64") (pinfunction "ZZ_64") (pintype "passive"))
      (node (ref "SRAM1") (pin "67") (pinfunction "VSS_67") (pintype "passive"))
      (node (ref "SRAM1") (pin "71") (pinfunction "VSS_71") (pintype "passive"))
      (node (ref "SRAM1") (pin "76") (pinfunction "VSS_76") (pintype "passive"))
      (node (ref "SRAM1") (pin "90") (pinfunction "VSS_90") (pintype "passive"))
      (node (ref "SRAM1") (pin "92") (pinfunction "CE3_92") (pintype "passive"))
      (node (ref "SRAM1") (pin "93") (pinfunction "BWA_93") (pintype "passive"))
      (node (ref "SRAM1") (pin "94") (pinfunction "BWB_94") (pintype "passive"))
      (node (ref "XC8") (pin "0") (pinfunction "M_0") (pintype "passive"))
      (node (ref "XC8") (pin "70") (pinfunction "70_70") (pintype "passive"))
      (node (ref "XC8") (pin "71") (pinfunction "71_71") (pintype "passive"))
      (node (ref "XC8") (pin "72") (pinfunction "72_72") (pintype "passive"))
      (node (ref "XC8") (pin "73") (pinfunction "73_73") (pintype "passive"))
      (node (ref "XC8") (pin "74") (pinfunction "74_74") (pintype "passive"))
      (node (ref "XC8") (pin "75") (pinfunction "75_75") (pintype "passive"))
      (node (ref "XC8") (pin "76") (pinfunction "76_76") (pintype "passive"))
      (node (ref "XC8") (pin "77") (pinfunction "77_77") (pintype "passive"))
      (node (ref "XC8") (pin "78") (pinfunction "78_78") (pintype "passive"))
      (node (ref "XC8") (pin "79") (pinfunction "79_79") (pintype "passive"))
      (node (ref "XC8") (pin "80") (pinfunction "80_80") (pintype "passive"))
    )
    (net (code "109") (name "unconnected-(FPGA1A-IO_25_12-PadW16)") (class "Default")
      (node (ref "FPGA1") (pin "W16") (pinfunction "IO_25_12_W16") (pintype "bidirectional"))
    )
    (net (code "110") (name "unconnected-(FPGA1A-IO_L1N_T0_12-PadAE26)") (class "Default")
      (node (ref "FPGA1") (pin "AE26") (pinfunction "IO_L1N_T0_12_AE26") (pintype "bidirectional"))
    )
    (net (code "111") (name "unconnected-(FPGA1A-IO_L15P_T2_DQS_12-PadAC18)") (class "Default")
      (node (ref "FPGA1") (pin "AC18") (pinfunction "IO_L15P_T2_DQS_12_AC18") (pintype "bidirectional"))
    )
    (net (code "112") (name "unconnected-(FPGA1A-IO_L21P_T3_DQS_12-PadY16)") (class "Default")
      (node (ref "FPGA1") (pin "Y16") (pinfunction "IO_L21P_T3_DQS_12_Y16") (pintype "bidirectional"))
    )
    (net (code "113") (name "unconnected-(FPGA1A-IO_L23P_T3_12-PadY15)") (class "Default")
      (node (ref "FPGA1") (pin "Y15") (pinfunction "IO_L23P_T3_12_Y15") (pintype "bidirectional"))
    )
    (net (code "114") (name "unconnected-(FPGA1A-IO_L24N_T3_12-PadW15)") (class "Default")
      (node (ref "FPGA1") (pin "W15") (pinfunction "IO_L24N_T3_12_W15") (pintype "bidirectional"))
    )
    (net (code "115") (name "unconnected-(FPGA1A-IO_L24P_T3_12-PadW14)") (class "Default")
      (node (ref "FPGA1") (pin "W14") (pinfunction "IO_L24P_T3_12_W14") (pintype "bidirectional"))
    )
    (net (code "116") (name "unconnected-(SRAM1C-NC-Pad1)") (class "Default")
      (node (ref "SRAM1") (pin "1") (pinfunction "NC_1") (pintype "passive"))
    )
    (net (code "117") (name "unconnected-(SRAM1C-NC-Pad2)") (class "Default")
      (node (ref "SRAM1") (pin "2") (pinfunction "NC_2") (pintype "passive"))
    )
    (net (code "118") (name "unconnected-(SRAM1C-NC-Pad3)") (class "Default")
      (node (ref "SRAM1") (pin "3") (pinfunction "NC_3") (pintype "passive"))
    )
    (net (code "119") (name "unconnected-(SRAM1C-NC-Pad6)") (class "Default")
      (node (ref "SRAM1") (pin "6") (pinfunction "NC_6") (pintype "passive"))
    )
    (net (code "120") (name "unconnected-(SRAM1C-NC-Pad7)") (class "Default")
      (node (ref "SRAM1") (pin "7") (pinfunction "NC_7") (pintype "passive"))
    )
    (net (code "121") (name "unconnected-(SRAM1C-NC-Pad10)") (class "Default")
      (node (ref "SRAM1") (pin "10") (pinfunction "NC_10") (pintype "passive"))
    )
    (net (code "122") (name "unconnected-(SRAM1C-NC-Pad14)") (class "Default")
      (node (ref "SRAM1") (pin "14") (pinfunction "NC_14") (pintype "passive"))
    )
    (net (code "123") (name "unconnected-(SRAM1C-NC-Pad16)") (class "Default")
      (node (ref "SRAM1") (pin "16") (pinfunction "NC_16") (pintype "passive"))
    )
    (net (code "124") (name "unconnected-(SRAM1C-NC-Pad25)") (class "Default")
      (node (ref "SRAM1") (pin "25") (pinfunction "NC_25") (pintype "passive"))
    )
    (net (code "125") (name "unconnected-(SRAM1C-NC-Pad28)") (class "Default")
      (node (ref "SRAM1") (pin "28") (pinfunction "NC_28") (pintype "passive"))
    )
    (net (code "126") (name "unconnected-(SRAM1C-NC-Pad29)") (class "Default")
      (node (ref "SRAM1") (pin "29") (pinfunction "NC_29") (pintype "passive"))
    )
    (net (code "127") (name "unconnected-(SRAM1C-NC-Pad30)") (class "Default")
      (node (ref "SRAM1") (pin "30") (pinfunction "NC_30") (pintype "passive"))
    )
    (net (code "128") (name "unconnected-(SRAM1C-NC-Pad38)") (class "Default")
      (node (ref "SRAM1") (pin "38") (pinfunction "NC_38") (pintype "passive"))
    )
    (net (code "129") (name "unconnected-(SRAM1C-NC-Pad39)") (class "Default")
      (node (ref "SRAM1") (pin "39") (pinfunction "NC_39") (pintype "passive"))
    )
    (net (code "130") (name "unconnected-(SRAM1C-NC-Pad42)") (class "Default")
      (node (ref "SRAM1") (pin "42") (pinfunction "NC_42") (pintype "passive"))
    )
    (net (code "131") (name "unconnected-(SRAM1C-NC-Pad43)") (class "Default")
      (node (ref "SRAM1") (pin "43") (pinfunction "NC_43") (pintype "passive"))
    )
    (net (code "132") (name "unconnected-(SRAM1C-NC-Pad51)") (class "Default")
      (node (ref "SRAM1") (pin "51") (pinfunction "NC_51") (pintype "passive"))
    )
    (net (code "133") (name "unconnected-(SRAM1C-NC-Pad52)") (class "Default")
      (node (ref "SRAM1") (pin "52") (pinfunction "NC_52") (pintype "passive"))
    )
    (net (code "134") (name "unconnected-(SRAM1C-NC-Pad53)") (class "Default")
      (node (ref "SRAM1") (pin "53") (pinfunction "NC_53") (pintype "passive"))
    )
    (net (code "135") (name "unconnected-(SRAM1C-NC-Pad56)") (class "Default")
      (node (ref "SRAM1") (pin "56") (pinfunction "NC_56") (pintype "passive"))
    )
    (net (code "136") (name "unconnected-(SRAM1C-NC-Pad57)") (class "Default")
      (node (ref "SRAM1") (pin "57") (pinfunction "NC_57") (pintype "passive"))
    )
    (net (code "137") (name "unconnected-(SRAM1C-NC-Pad66)") (class "Default")
      (node (ref "SRAM1") (pin "66") (pinfunction "NC_66") (pintype "passive"))
    )
    (net (code "138") (name "unconnected-(SRAM1C-NC-Pad75)") (class "Default")
      (node (ref "SRAM1") (pin "75") (pinfunction "NC_75") (pintype "passive"))
    )
    (net (code "139") (name "unconnected-(SRAM1C-NC-Pad78)") (class "Default")
      (node (ref "SRAM1") (pin "78") (pinfunction "NC_78") (pintype "passive"))
    )
    (net (code "140") (name "unconnected-(SRAM1C-NC-Pad79)") (class "Default")
      (node (ref "SRAM1") (pin "79") (pinfunction "NC_79") (pintype "passive"))
    )
    (net (code "141") (name "unconnected-(SRAM1C-NC-Pad84)") (class "Default")
      (node (ref "SRAM1") (pin "84") (pinfunction "NC_84") (pintype "passive"))
    )
    (net (code "142") (name "unconnected-(SRAM1C-NC-Pad95)") (class "Default")
      (node (ref "SRAM1") (pin "95") (pinfunction "NC_95") (pintype "passive"))
    )
    (net (code "143") (name "unconnected-(SRAM1C-NC-Pad96)") (class "Default")
      (node (ref "SRAM1") (pin "96") (pinfunction "NC_96") (pintype "passive"))
    )
  )
)
